# schematic.net
KiCad netlist of a schematic drawn in EasyEDA
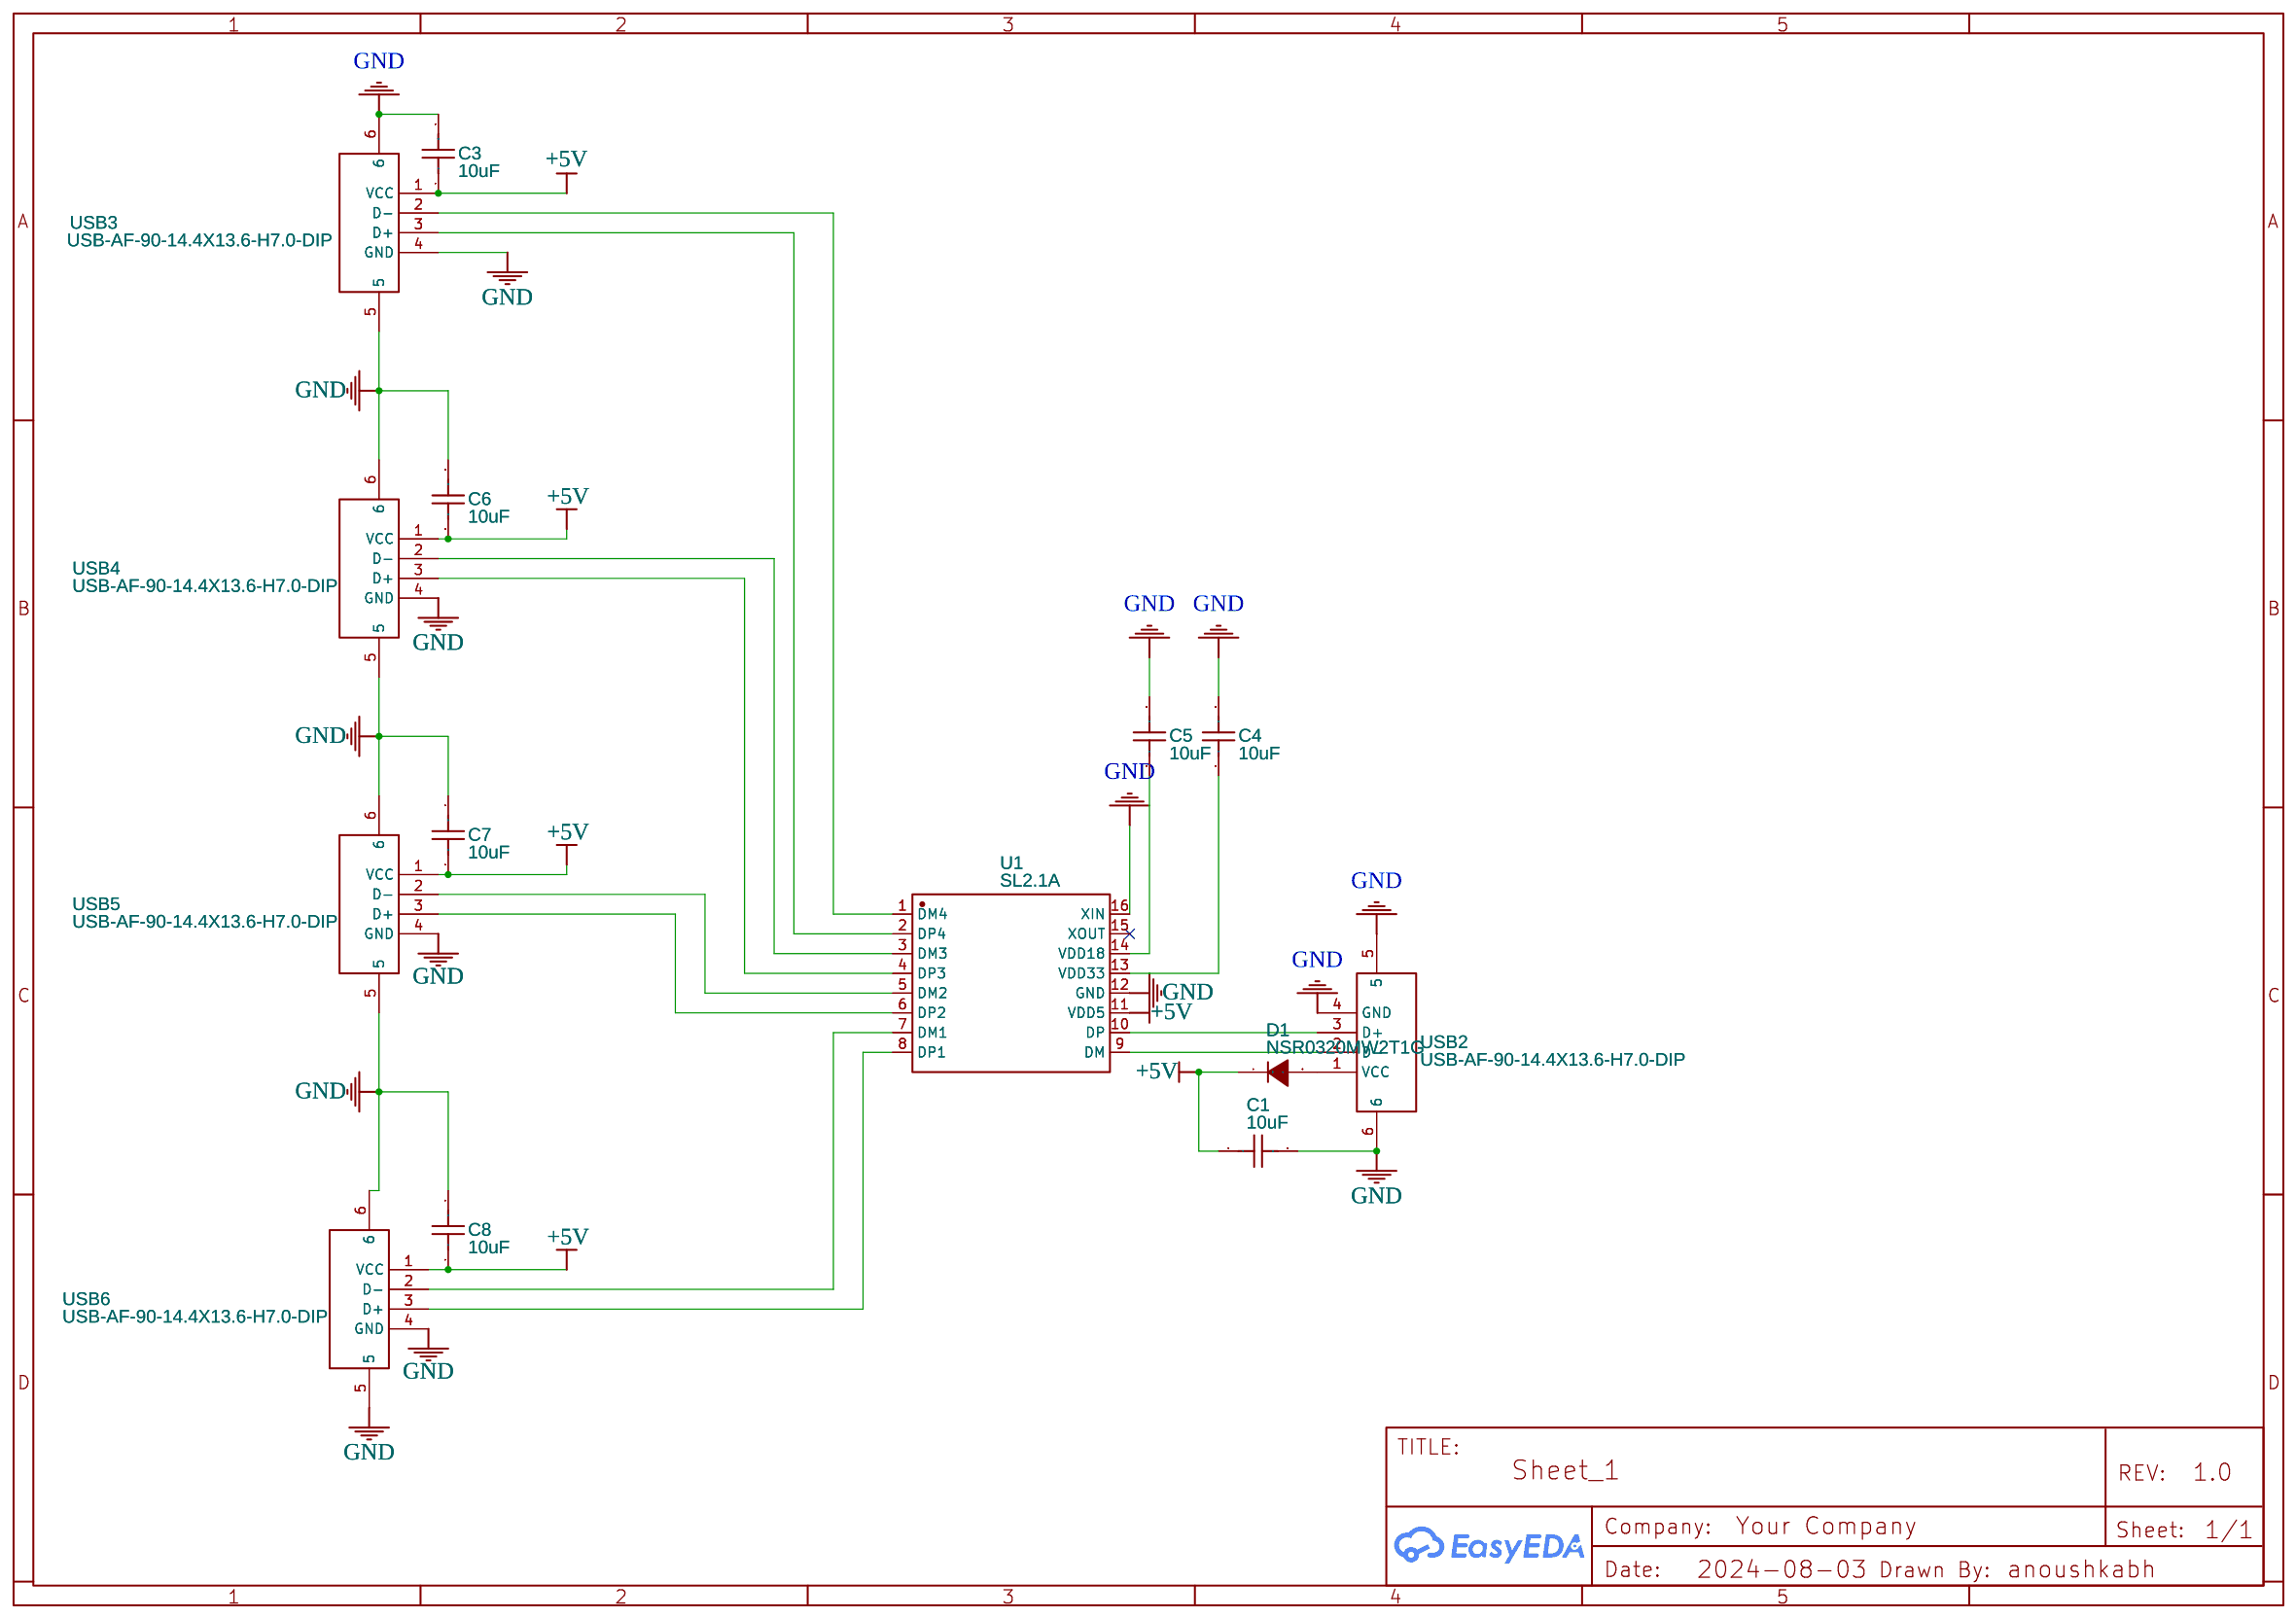
[diagram p0: schematic sheet]

(export (version "E")
  (design (tool "Eeschema 10.0.6"))
  (components
    (comp (ref "C1")
      (value "10uF")
      (fields
        (field (name "Manufacturer Part") "CL10A106KP8NNNC")
        (field (name "Manufacturer") "SAMSUNG(三星)")
      )
      (libsource (lib "") (part "CL10A106KP8NNNC_1"))
    )
    (comp (ref "C3")
      (value "10uF")
      (fields
        (field (name "Manufacturer Part") "CL10A106KP8NNNC")
        (field (name "Manufacturer") "SAMSUNG(三星)")
      )
      (libsource (lib "") (part "CL10A106KP8NNNC"))
    )
    (comp (ref "C4")
      (value "10uF")
      (fields
        (field (name "Manufacturer Part") "CL10A106KP8NNNC")
        (field (name "Manufacturer") "SAMSUNG(三星)")
      )
      (libsource (lib "") (part "CL10A106KP8NNNC"))
    )
    (comp (ref "C5")
      (value "10uF")
      (fields
        (field (name "Manufacturer Part") "CL10A106KP8NNNC")
        (field (name "Manufacturer") "SAMSUNG(三星)")
      )
      (libsource (lib "") (part "CL10A106KP8NNNC"))
    )
    (comp (ref "C6")
      (value "10uF")
      (fields
        (field (name "Manufacturer Part") "CL10A106KP8NNNC")
        (field (name "Manufacturer") "SAMSUNG(三星)")
      )
      (libsource (lib "") (part "CL10A106KP8NNNC"))
    )
    (comp (ref "C7")
      (value "10uF")
      (fields
        (field (name "Manufacturer Part") "CL10A106KP8NNNC")
        (field (name "Manufacturer") "SAMSUNG(三星)")
      )
      (libsource (lib "") (part "CL10A106KP8NNNC"))
    )
    (comp (ref "C8")
      (value "10uF")
      (fields
        (field (name "Manufacturer Part") "CL10A106KP8NNNC")
        (field (name "Manufacturer") "SAMSUNG(三星)")
      )
      (libsource (lib "") (part "CL10A106KP8NNNC"))
    )
    (comp (ref "D1")
      (value "NSR0320MW2T1G")
      (fields (field (name "Manufacturer") "onsemi(安森美)"))
      (libsource (lib "") (part "NSR0320MW2T1G"))
    )
    (comp (ref "U1")
      (value "SL2.1A")
      (fields (field (name "Manufacturer") "CoreChips(和芯润德)"))
      (libsource (lib "") (part "SL2.1A"))
    )
    (comp (ref "USB2")
      (value "USB-AF-90-14.4X13.6-H7.0-DIP")
      (fields (field (name "Manufacturer Part") "903-131A1011D10100") (field (name "Manufacturer") "精拓金"))
      (libsource (lib "") (part "USB-AF-90-14.4X13.6-H7.0-DIP_1"))
    )
    (comp (ref "USB3")
      (value "USB-AF-90-14.4X13.6-H7.0-DIP")
      (fields (field (name "Manufacturer Part") "903-131A1011D10100") (field (name "Manufacturer") "精拓金"))
      (libsource (lib "") (part "USB-AF-90-14.4X13.6-H7.0-DIP"))
    )
    (comp (ref "USB4")
      (value "USB-AF-90-14.4X13.6-H7.0-DIP")
      (fields (field (name "Manufacturer Part") "903-131A1011D10100") (field (name "Manufacturer") "精拓金"))
      (libsource (lib "") (part "USB-AF-90-14.4X13.6-H7.0-DIP"))
    )
    (comp (ref "USB5")
      (value "USB-AF-90-14.4X13.6-H7.0-DIP")
      (fields (field (name "Manufacturer Part") "903-131A1011D10100") (field (name "Manufacturer") "精拓金"))
      (libsource (lib "") (part "USB-AF-90-14.4X13.6-H7.0-DIP"))
    )
    (comp (ref "USB6")
      (value "USB-AF-90-14.4X13.6-H7.0-DIP")
      (fields (field (name "Manufacturer Part") "903-131A1011D10100") (field (name "Manufacturer") "精拓金"))
      (libsource (lib "") (part "USB-AF-90-14.4X13.6-H7.0-DIP"))
    )
  )
  (nets
    (net (code "1") (name "+5V") (class "Default")
      (node (ref "C1") (pin "1") (pinfunction "1_1") (pintype "unspecified"))
      (node (ref "C3") (pin "1") (pinfunction "1_1") (pintype "unspecified"))
      (node (ref "C6") (pin "1") (pinfunction "1_1") (pintype "unspecified"))
      (node (ref "C7") (pin "1") (pinfunction "1_1") (pintype "unspecified"))
      (node (ref "C8") (pin "1") (pinfunction "1_1") (pintype "unspecified"))
      (node (ref "D1") (pin "1") (pinfunction "C_1") (pintype "unspecified"))
      (node (ref "U1") (pin "11") (pinfunction "VDD5_11") (pintype "unspecified"))
      (node (ref "USB3") (pin "1") (pinfunction "VCC_1") (pintype "unspecified"))
      (node (ref "USB4") (pin "1") (pinfunction "VCC_1") (pintype "unspecified"))
      (node (ref "USB5") (pin "1") (pinfunction "VCC_1") (pintype "unspecified"))
      (node (ref "USB6") (pin "1") (pinfunction "VCC_1") (pintype "unspecified"))
    )
    (net (code "2") (name "GND") (class "Default")
      (node (ref "C1") (pin "2") (pinfunction "2_2") (pintype "unspecified"))
      (node (ref "C3") (pin "2") (pinfunction "2_2") (pintype "unspecified"))
      (node (ref "C4") (pin "2") (pinfunction "2_2") (pintype "unspecified"))
      (node (ref "C5") (pin "2") (pinfunction "2_2") (pintype "unspecified"))
      (node (ref "C6") (pin "2") (pinfunction "2_2") (pintype "unspecified"))
      (node (ref "C7") (pin "2") (pinfunction "2_2") (pintype "unspecified"))
      (node (ref "C8") (pin "2") (pinfunction "2_2") (pintype "unspecified"))
      (node (ref "U1") (pin "12") (pinfunction "GND_12") (pintype "unspecified"))
      (node (ref "U1") (pin "16") (pinfunction "XIN_16") (pintype "unspecified"))
      (node (ref "USB2") (pin "4") (pinfunction "GND_4") (pintype "unspecified"))
      (node (ref "USB2") (pin "5") (pinfunction "5_5") (pintype "unspecified"))
      (node (ref "USB2") (pin "6") (pinfunction "6_6") (pintype "unspecified"))
      (node (ref "USB3") (pin "4") (pinfunction "GND_4") (pintype "unspecified"))
      (node (ref "USB3") (pin "5") (pinfunction "5_5") (pintype "unspecified"))
      (node (ref "USB3") (pin "6") (pinfunction "6_6") (pintype "unspecified"))
      (node (ref "USB4") (pin "4") (pinfunction "GND_4") (pintype "unspecified"))
      (node (ref "USB4") (pin "5") (pinfunction "5_5") (pintype "unspecified"))
      (node (ref "USB4") (pin "6") (pinfunction "6_6") (pintype "unspecified"))
      (node (ref "USB5") (pin "4") (pinfunction "GND_4") (pintype "unspecified"))
      (node (ref "USB5") (pin "5") (pinfunction "5_5") (pintype "unspecified"))
      (node (ref "USB5") (pin "6") (pinfunction "6_6") (pintype "unspecified"))
      (node (ref "USB6") (pin "4") (pinfunction "GND_4") (pintype "unspecified"))
      (node (ref "USB6") (pin "5") (pinfunction "5_5") (pintype "unspecified"))
      (node (ref "USB6") (pin "6") (pinfunction "6_6") (pintype "unspecified"))
    )
    (net (code "3") (name "Net-(D1-A)") (class "Default")
      (node (ref "D1") (pin "2") (pinfunction "A_2") (pintype "unspecified"))
      (node (ref "USB2") (pin "1") (pinfunction "VCC_1") (pintype "unspecified"))
    )
    (net (code "4") (name "Net-(U1-DM)") (class "Default")
      (node (ref "U1") (pin "9") (pinfunction "DM_9") (pintype "unspecified"))
      (node (ref "USB2") (pin "2") (pinfunction "D-_2") (pintype "unspecified"))
    )
    (net (code "5") (name "Net-(U1-DM1)") (class "Default")
      (node (ref "U1") (pin "7") (pinfunction "DM1_7") (pintype "unspecified"))
      (node (ref "USB6") (pin "2") (pinfunction "D-_2") (pintype "unspecified"))
    )
    (net (code "6") (name "Net-(U1-DM2)") (class "Default")
      (node (ref "U1") (pin "5") (pinfunction "DM2_5") (pintype "unspecified"))
      (node (ref "USB5") (pin "2") (pinfunction "D-_2") (pintype "unspecified"))
    )
    (net (code "7") (name "Net-(U1-DM3)") (class "Default")
      (node (ref "U1") (pin "3") (pinfunction "DM3_3") (pintype "unspecified"))
      (node (ref "USB4") (pin "2") (pinfunction "D-_2") (pintype "unspecified"))
    )
    (net (code "8") (name "Net-(U1-DM4)") (class "Default")
      (node (ref "U1") (pin "1") (pinfunction "DM4_1") (pintype "unspecified"))
      (node (ref "USB3") (pin "2") (pinfunction "D-_2") (pintype "unspecified"))
    )
    (net (code "9") (name "Net-(U1-DP)") (class "Default")
      (node (ref "U1") (pin "10") (pinfunction "DP_10") (pintype "unspecified"))
      (node (ref "USB2") (pin "3") (pinfunction "D+_3") (pintype "unspecified"))
    )
    (net (code "10") (name "Net-(U1-DP1)") (class "Default")
      (node (ref "U1") (pin "8") (pinfunction "DP1_8") (pintype "unspecified"))
      (node (ref "USB6") (pin "3") (pinfunction "D+_3") (pintype "unspecified"))
    )
    (net (code "11") (name "Net-(U1-DP2)") (class "Default")
      (node (ref "U1") (pin "6") (pinfunction "DP2_6") (pintype "unspecified"))
      (node (ref "USB5") (pin "3") (pinfunction "D+_3") (pintype "unspecified"))
    )
    (net (code "12") (name "Net-(U1-DP3)") (class "Default")
      (node (ref "U1") (pin "4") (pinfunction "DP3_4") (pintype "unspecified"))
      (node (ref "USB4") (pin "3") (pinfunction "D+_3") (pintype "unspecified"))
    )
    (net (code "13") (name "Net-(U1-DP4)") (class "Default")
      (node (ref "U1") (pin "2") (pinfunction "DP4_2") (pintype "unspecified"))
      (node (ref "USB3") (pin "3") (pinfunction "D+_3") (pintype "unspecified"))
    )
    (net (code "14") (name "Net-(U1-VDD18)") (class "Default")
      (node (ref "C5") (pin "1") (pinfunction "1_1") (pintype "unspecified"))
      (node (ref "U1") (pin "14") (pinfunction "VDD18_14") (pintype "unspecified"))
    )
    (net (code "15") (name "Net-(U1-VDD33)") (class "Default")
      (node (ref "C4") (pin "1") (pinfunction "1_1") (pintype "unspecified"))
      (node (ref "U1") (pin "13") (pinfunction "VDD33_13") (pintype "unspecified"))
    )
    (net (code "16") (name "unconnected-(U1-XOUT-Pad15)") (class "Default")
      (node (ref "U1") (pin "15") (pinfunction "XOUT_15") (pintype "unspecified+no_connect"))
    )
  )
)
